# substractor-741_p-stm-v1_0.net
KiCad netlist of a schematic drawn in EAGLE
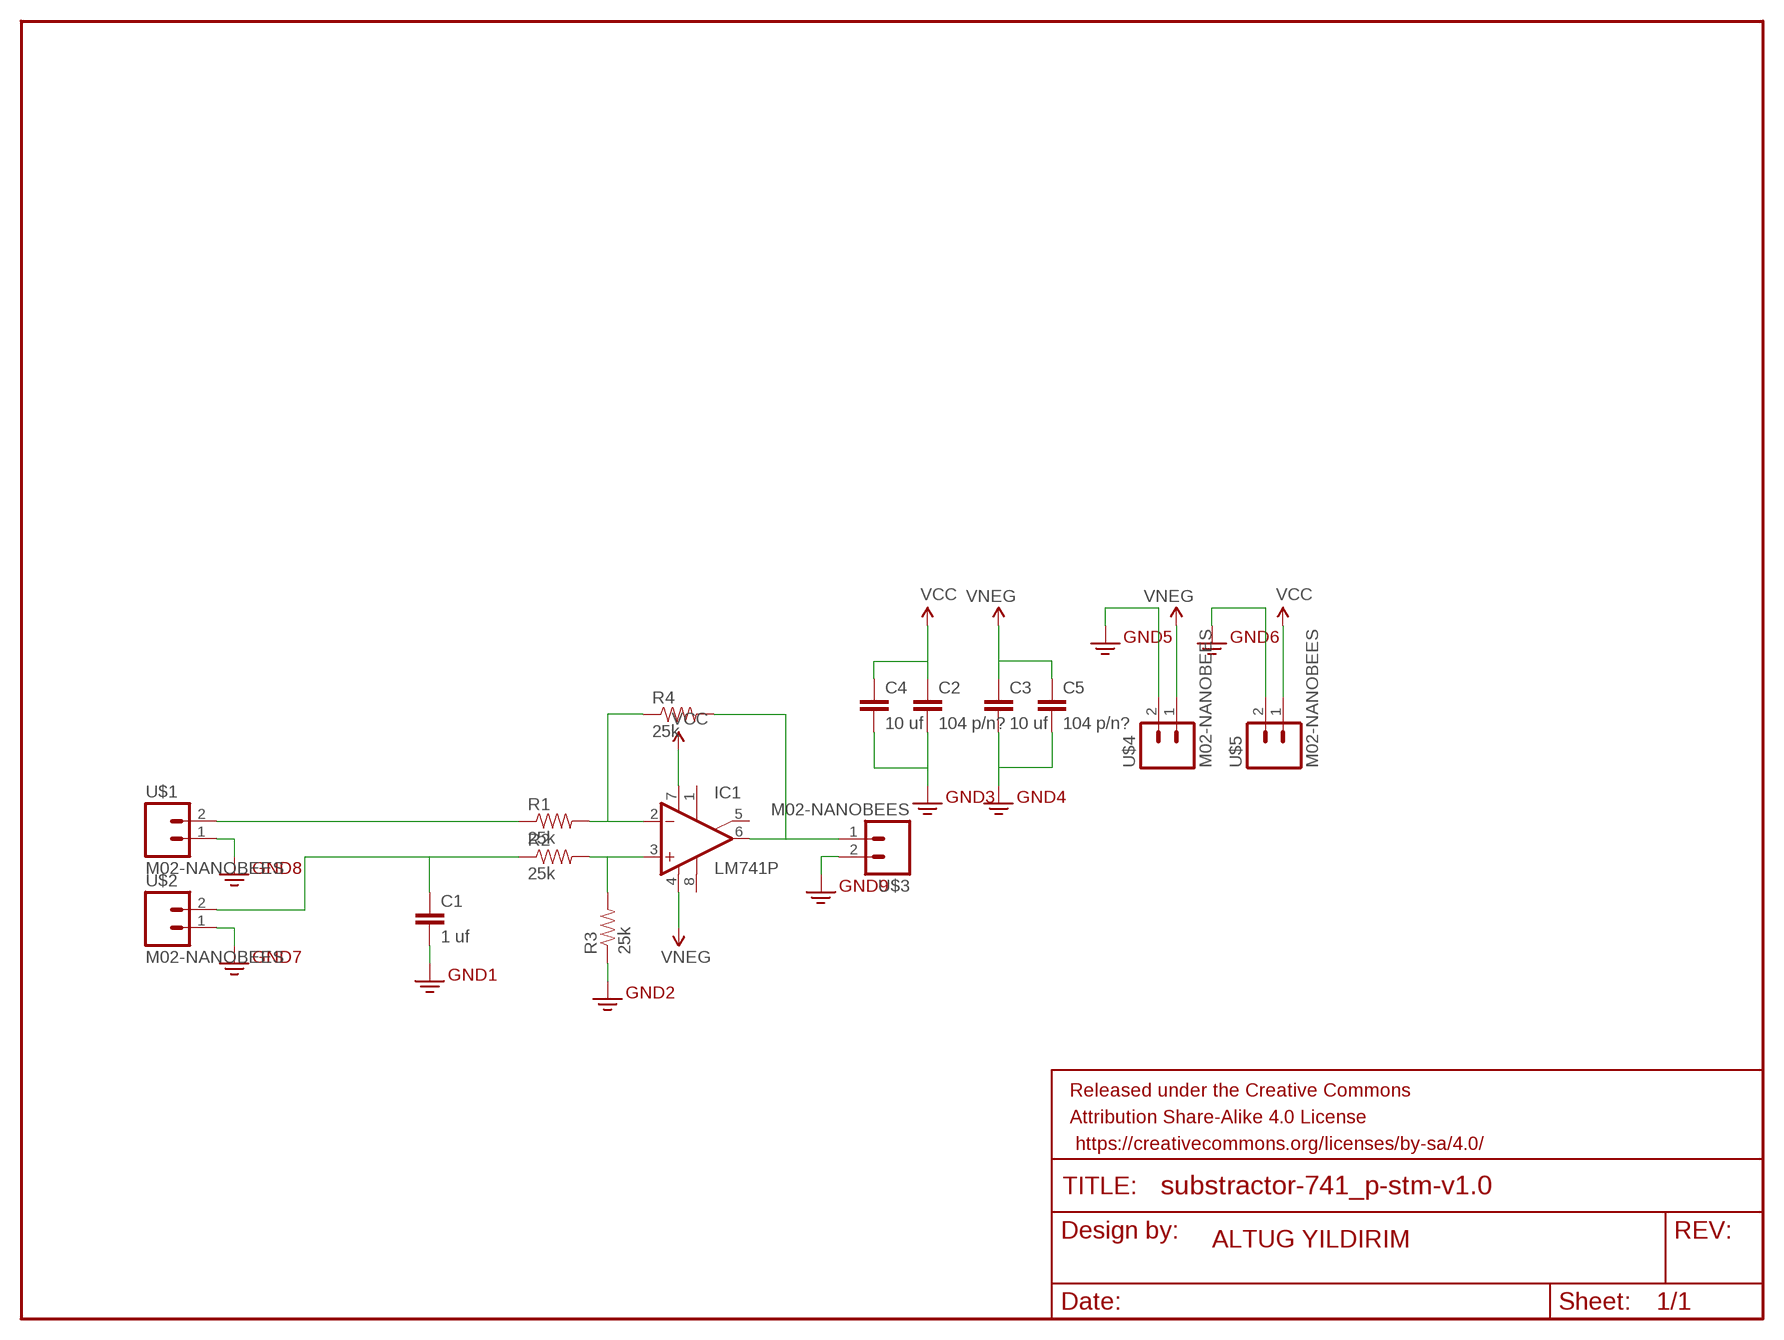
[diagram p0: schematic, sheet 1]

(export (version "E")
  (design (tool "Eeschema 10.0.6"))
  (components
    (comp (ref "C1")
      (value "1 uf")
      (footprint "eagle-import:CAP-PTH-SMALL2")
      (libsource (lib "eagle-import") (part "CAPPTH2"))
    )
    (comp (ref "C2")
      (value "104 p/n?")
      (footprint "eagle-import:CAP-PTH-SMALL2")
      (libsource (lib "eagle-import") (part "CAPPTH2"))
    )
    (comp (ref "C3")
      (value "10 uf")
      (footprint "eagle-import:CAP-PTH-SMALL2")
      (libsource (lib "eagle-import") (part "CAPPTH2"))
    )
    (comp (ref "C4")
      (value "10 uf")
      (footprint "eagle-import:CAP-PTH-SMALL2")
      (libsource (lib "eagle-import") (part "CAPPTH2"))
    )
    (comp (ref "C5")
      (value "104 p/n?")
      (footprint "eagle-import:CAP-PTH-SMALL2")
      (libsource (lib "eagle-import") (part "CAPPTH2"))
    )
    (comp (ref "FRAME1")
      (value "FRAME-LETTER")
      (footprint "eagle-import:CREATIVE_COMMONS")
      (libsource (lib "eagle-import") (part "FRAME-LETTER"))
    )
    (comp (ref "IC1")
      (value "LM741P")
      (footprint "eagle-import:DIL08")
      (libsource (lib "eagle-import") (part "741PLM"))
    )
    (comp (ref "R1")
      (value "25k")
      (footprint "eagle-import:AXIAL-0.4")
      (libsource (lib "eagle-import") (part "RESISTORPTH-1/4W"))
    )
    (comp (ref "R2")
      (value "25k")
      (footprint "eagle-import:AXIAL-0.4")
      (libsource (lib "eagle-import") (part "RESISTORPTH-1/4W"))
    )
    (comp (ref "R3")
      (value "25k")
      (footprint "eagle-import:AXIAL-0.4")
      (libsource (lib "eagle-import") (part "RESISTORPTH-1/4W"))
    )
    (comp (ref "R4")
      (value "25k")
      (footprint "eagle-import:AXIAL-0.4")
      (libsource (lib "eagle-import") (part "RESISTORPTH-1/4W"))
    )
    (comp (ref "U$1")
      (value "M02-NANOBEES")
      (footprint "eagle-import:M02-NANOBEES")
      (libsource (lib "eagle-import") (part "M02-NANOBEES"))
    )
    (comp (ref "U$2")
      (value "M02-NANOBEES")
      (footprint "eagle-import:M02-NANOBEES")
      (libsource (lib "eagle-import") (part "M02-NANOBEES"))
    )
    (comp (ref "U$3")
      (value "M02-NANOBEES")
      (footprint "eagle-import:M02-NANOBEES")
      (libsource (lib "eagle-import") (part "M02-NANOBEES"))
    )
    (comp (ref "U$4")
      (value "M02-NANOBEES")
      (footprint "eagle-import:M02-NANOBEES")
      (libsource (lib "eagle-import") (part "M02-NANOBEES"))
    )
    (comp (ref "U$5")
      (value "M02-NANOBEES")
      (footprint "eagle-import:M02-NANOBEES")
      (libsource (lib "eagle-import") (part "M02-NANOBEES"))
    )
  )
  (nets
    (net (code "1") (name "GND2") (class "Default")
      (node (ref "C1") (pin "2") (pinfunction "2_2") (pintype "passive"))
      (node (ref "C2") (pin "2") (pinfunction "2_2") (pintype "passive"))
      (node (ref "C3") (pin "2") (pinfunction "2_2") (pintype "passive"))
      (node (ref "C4") (pin "2") (pinfunction "2_2") (pintype "passive"))
      (node (ref "C5") (pin "2") (pinfunction "2_2") (pintype "passive"))
      (node (ref "R3") (pin "P$1") (pinfunction "1_P$1") (pintype "passive"))
      (node (ref "U$1") (pin "1") (pinfunction "1_1") (pintype "passive"))
      (node (ref "U$2") (pin "1") (pinfunction "1_1") (pintype "passive"))
      (node (ref "U$3") (pin "2") (pinfunction "2_2") (pintype "passive"))
      (node (ref "U$4") (pin "2") (pinfunction "2_2") (pintype "passive"))
      (node (ref "U$5") (pin "2") (pinfunction "2_2") (pintype "passive"))
    )
    (net (code "2") (name "Net-(IC1-+IN)") (class "Default")
      (node (ref "IC1") (pin "2") (pinfunction "+IN_2") (pintype "input"))
      (node (ref "R1") (pin "P$2") (pinfunction "2_P$2") (pintype "passive"))
      (node (ref "R4") (pin "P$1") (pinfunction "1_P$1") (pintype "passive"))
    )
    (net (code "3") (name "Net-(IC1--IN)") (class "Default")
      (node (ref "IC1") (pin "3") (pinfunction "-IN_3") (pintype "input"))
      (node (ref "R2") (pin "P$2") (pinfunction "2_P$2") (pintype "passive"))
      (node (ref "R3") (pin "P$2") (pinfunction "2_P$2") (pintype "passive"))
    )
    (net (code "4") (name "Net-(IC1-OUT)") (class "Default")
      (node (ref "IC1") (pin "6") (pinfunction "OUT_6") (pintype "output"))
      (node (ref "R4") (pin "P$2") (pinfunction "2_P$2") (pintype "passive"))
      (node (ref "U$3") (pin "1") (pinfunction "1_1") (pintype "passive"))
    )
    (net (code "5") (name "Net-(R1-1)") (class "Default")
      (node (ref "R1") (pin "P$1") (pinfunction "1_P$1") (pintype "passive"))
      (node (ref "U$1") (pin "2") (pinfunction "2_2") (pintype "passive"))
    )
    (net (code "6") (name "Net-(R2-1)") (class "Default")
      (node (ref "C1") (pin "1") (pinfunction "1_1") (pintype "passive"))
      (node (ref "R2") (pin "P$1") (pinfunction "1_P$1") (pintype "passive"))
      (node (ref "U$2") (pin "2") (pinfunction "2_2") (pintype "passive"))
    )
    (net (code "7") (name "VCC") (class "Default")
      (node (ref "C2") (pin "1") (pinfunction "1_1") (pintype "passive"))
      (node (ref "C4") (pin "1") (pinfunction "1_1") (pintype "passive"))
      (node (ref "IC1") (pin "7") (pinfunction "V+_7") (pintype "power_in"))
      (node (ref "U$5") (pin "1") (pinfunction "1_1") (pintype "passive"))
    )
    (net (code "8") (name "VNEG") (class "Default")
      (node (ref "C3") (pin "1") (pinfunction "1_1") (pintype "passive"))
      (node (ref "C5") (pin "1") (pinfunction "1_1") (pintype "passive"))
      (node (ref "IC1") (pin "4") (pinfunction "V-_4") (pintype "power_in"))
      (node (ref "U$4") (pin "1") (pinfunction "1_1") (pintype "passive"))
    )
    (net (code "9") (name "unconnected-(IC1-ON1-Pad1)") (class "Default")
      (node (ref "IC1") (pin "1") (pinfunction "ON1_1") (pintype "passive"))
    )
    (net (code "10") (name "unconnected-(IC1-ON2-Pad5)") (class "Default")
      (node (ref "IC1") (pin "5") (pinfunction "ON2_5") (pintype "passive"))
    )
    (net (code "11") (name "unconnected-(IC1-OPT-Pad8)") (class "Default")
      (node (ref "IC1") (pin "8") (pinfunction "OPT_8") (pintype "passive"))
    )
  )
)
